# Back.net
KiCad netlist of a schematic drawn in Altium Designer
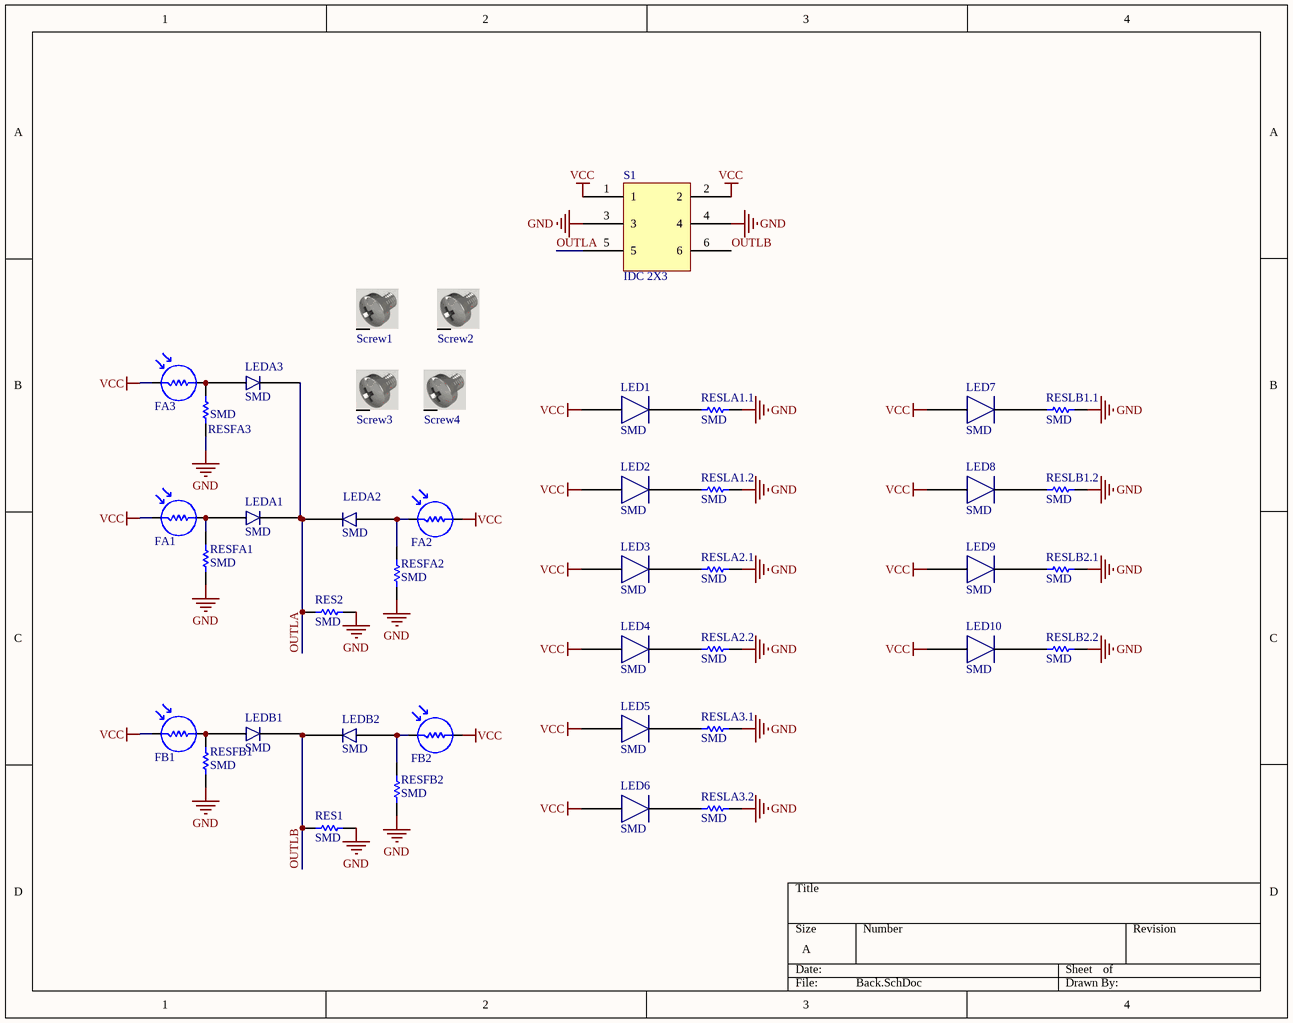
[diagram p0: Back.SchDoc]

(export (version "E")
  (design (tool "Eeschema 10.0.6"))
  (components
    (comp (ref "FA1")
      (value "Photo Cell")
      (footprint "PhotoCell.")
      (fields (field (name "PUBLISHER") "Altium Limited"))
      (libsource (lib "Farzanegan") (part "Photo Cell.."))
    )
    (comp (ref "FA2")
      (value "Photo Cell")
      (footprint "PhotoCell.")
      (fields (field (name "PUBLISHER") "Altium Limited"))
      (libsource (lib "Farzanegan") (part "Photo Cell.."))
    )
    (comp (ref "FA3")
      (value "Photo Cell")
      (footprint "PhotoCell.")
      (fields (field (name "PUBLISHER") "Altium Limited"))
      (libsource (lib "Farzanegan") (part "Photo Cell.."))
    )
    (comp (ref "FB1")
      (value "Photo Cell")
      (footprint "PhotoCell.")
      (fields (field (name "PUBLISHER") "Altium Limited"))
      (libsource (lib "Farzanegan") (part "Photo Cell.."))
    )
    (comp (ref "FB2")
      (value "Photo Cell")
      (footprint "PhotoCell.")
      (fields (field (name "PUBLISHER") "Altium Limited"))
      (libsource (lib "Farzanegan") (part "Photo Cell.."))
    )
    (comp (ref "LED1") (value "SMD") (footprint "LED SMD") (libsource (lib "Farzanegan") (part "LED SMD")))
    (comp (ref "LED2") (value "SMD") (footprint "LED SMD") (libsource (lib "Farzanegan") (part "LED SMD")))
    (comp (ref "LED3") (value "SMD") (footprint "LED SMD") (libsource (lib "Farzanegan") (part "LED SMD")))
    (comp (ref "LED4") (value "SMD") (footprint "LED SMD") (libsource (lib "Farzanegan") (part "LED SMD")))
    (comp (ref "LED5") (value "SMD") (footprint "LED SMD") (libsource (lib "Farzanegan") (part "LED SMD")))
    (comp (ref "LED6") (value "SMD") (footprint "LED SMD") (libsource (lib "Farzanegan") (part "LED SMD")))
    (comp (ref "LED7") (value "SMD") (footprint "LED SMD") (libsource (lib "Farzanegan") (part "LED SMD")))
    (comp (ref "LED8") (value "SMD") (footprint "LED SMD") (libsource (lib "Farzanegan") (part "LED SMD")))
    (comp (ref "LED9") (value "SMD") (footprint "LED SMD") (libsource (lib "Farzanegan") (part "LED SMD")))
    (comp (ref "LED10") (value "SMD") (footprint "LED SMD") (libsource (lib "Farzanegan") (part "LED SMD")))
    (comp (ref "LEDA1") (value "SMD") (footprint "LED SMD") (libsource (lib "") (part "LED SMD_1")))
    (comp (ref "LEDA2") (value "SMD") (footprint "LED SMD") (libsource (lib "") (part "LED SMD_1")))
    (comp (ref "LEDA3") (value "SMD") (footprint "LED SMD") (libsource (lib "") (part "LED SMD_1")))
    (comp (ref "LEDB1") (value "SMD") (footprint "LED SMD") (libsource (lib "") (part "LED SMD_1")))
    (comp (ref "LEDB2") (value "SMD") (footprint "LED SMD") (libsource (lib "") (part "LED SMD_1")))
    (comp (ref "RES1")
      (value "SMD")
      (footprint "Resistor SMD 1206")
      (libsource (lib "Farzanegan") (part "Res SMD"))
    )
    (comp (ref "RES2")
      (value "SMD")
      (footprint "Resistor SMD 1206")
      (libsource (lib "Farzanegan") (part "Res SMD"))
    )
    (comp (ref "RESFA1")
      (value "SMD")
      (footprint "Resistor SMD 1206")
      (libsource (lib "Farzanegan") (part "Res SMD"))
    )
    (comp (ref "RESFA2")
      (value "SMD")
      (footprint "Resistor SMD 1206")
      (libsource (lib "Farzanegan") (part "Res SMD"))
    )
    (comp (ref "RESFA3")
      (value "SMD")
      (footprint "Resistor SMD 1206")
      (libsource (lib "Farzanegan") (part "Res SMD"))
    )
    (comp (ref "RESFB1")
      (value "SMD")
      (footprint "Resistor SMD 1206")
      (libsource (lib "Farzanegan") (part "Res SMD"))
    )
    (comp (ref "RESFB2")
      (value "SMD")
      (footprint "Resistor SMD 1206")
      (libsource (lib "Farzanegan") (part "Res SMD"))
    )
    (comp (ref "RESLA1.1")
      (value "SMD")
      (footprint "Resistor SMD 1206")
      (libsource (lib "Farzanegan") (part "Res SMD"))
    )
    (comp (ref "RESLA1.2")
      (value "SMD")
      (footprint "Resistor SMD 1206")
      (libsource (lib "Farzanegan") (part "Res SMD"))
    )
    (comp (ref "RESLA2.1")
      (value "SMD")
      (footprint "Resistor SMD 1206")
      (libsource (lib "Farzanegan") (part "Res SMD"))
    )
    (comp (ref "RESLA2.2")
      (value "SMD")
      (footprint "Resistor SMD 1206")
      (libsource (lib "Farzanegan") (part "Res SMD"))
    )
    (comp (ref "RESLA3.1")
      (value "SMD")
      (footprint "Resistor SMD 1206")
      (libsource (lib "Farzanegan") (part "Res SMD"))
    )
    (comp (ref "RESLA3.2")
      (value "SMD")
      (footprint "Resistor SMD 1206")
      (libsource (lib "Farzanegan") (part "Res SMD"))
    )
    (comp (ref "RESLB1.1")
      (value "SMD")
      (footprint "Resistor SMD 1206")
      (libsource (lib "Farzanegan") (part "Res SMD"))
    )
    (comp (ref "RESLB1.2")
      (value "SMD")
      (footprint "Resistor SMD 1206")
      (libsource (lib "Farzanegan") (part "Res SMD"))
    )
    (comp (ref "RESLB2.1")
      (value "SMD")
      (footprint "Resistor SMD 1206")
      (libsource (lib "Farzanegan") (part "Res SMD"))
    )
    (comp (ref "RESLB2.2")
      (value "SMD")
      (footprint "Resistor SMD 1206")
      (libsource (lib "Farzanegan") (part "Res SMD"))
    )
    (comp (ref "S1") (value "IDC 2X3") (footprint "IDC 2X3") (libsource (lib "Farzanegan") (part "IDC 2X3")))
    (comp (ref "Screw1")
      (value "Screw")
      (footprint "Screw")
      (fields (field (name "PUBLISHER") "Altium Limited"))
      (libsource (lib "Farzanegan") (part "Screw"))
    )
    (comp (ref "Screw2")
      (value "Screw")
      (footprint "Screw")
      (fields (field (name "PUBLISHER") "Altium Limited"))
      (libsource (lib "Farzanegan") (part "Screw"))
    )
    (comp (ref "Screw3")
      (value "Screw")
      (footprint "Screw")
      (fields (field (name "PUBLISHER") "Altium Limited"))
      (libsource (lib "Farzanegan") (part "Screw"))
    )
    (comp (ref "Screw4")
      (value "Screw")
      (footprint "Screw")
      (fields (field (name "PUBLISHER") "Altium Limited"))
      (libsource (lib "Farzanegan") (part "Screw"))
    )
  )
  (nets
    (net (code "1") (name "/OUTLA") (class "Default")
      (node (ref "LEDA1") (pin "2") (pinfunction "2_2") (pintype "passive"))
      (node (ref "LEDA2") (pin "2") (pinfunction "2_2") (pintype "passive"))
      (node (ref "LEDA3") (pin "2") (pinfunction "2_2") (pintype "passive"))
      (node (ref "RES2") (pin "1") (pinfunction "1_1") (pintype "passive"))
      (node (ref "S1") (pin "5") (pinfunction "5_5") (pintype "passive"))
    )
    (net (code "2") (name "/OUTLB") (class "Default")
      (node (ref "LEDB1") (pin "2") (pinfunction "2_2") (pintype "passive"))
      (node (ref "LEDB2") (pin "2") (pinfunction "2_2") (pintype "passive"))
      (node (ref "RES1") (pin "1") (pinfunction "1_1") (pintype "passive"))
      (node (ref "S1") (pin "6") (pinfunction "6_6") (pintype "passive"))
    )
    (net (code "3") (name "GND") (class "Default")
      (node (ref "RES1") (pin "2") (pinfunction "2_2") (pintype "passive"))
      (node (ref "RES2") (pin "2") (pinfunction "2_2") (pintype "passive"))
      (node (ref "RESFA1") (pin "1") (pinfunction "1_1") (pintype "passive"))
      (node (ref "RESFA2") (pin "1") (pinfunction "1_1") (pintype "passive"))
      (node (ref "RESFA3") (pin "1") (pinfunction "1_1") (pintype "passive"))
      (node (ref "RESFB1") (pin "1") (pinfunction "1_1") (pintype "passive"))
      (node (ref "RESFB2") (pin "1") (pinfunction "1_1") (pintype "passive"))
      (node (ref "RESLA1.1") (pin "2") (pinfunction "2_2") (pintype "passive"))
      (node (ref "RESLA1.2") (pin "2") (pinfunction "2_2") (pintype "passive"))
      (node (ref "RESLA2.1") (pin "2") (pinfunction "2_2") (pintype "passive"))
      (node (ref "RESLA2.2") (pin "2") (pinfunction "2_2") (pintype "passive"))
      (node (ref "RESLA3.1") (pin "2") (pinfunction "2_2") (pintype "passive"))
      (node (ref "RESLA3.2") (pin "2") (pinfunction "2_2") (pintype "passive"))
      (node (ref "RESLB1.1") (pin "2") (pinfunction "2_2") (pintype "passive"))
      (node (ref "RESLB1.2") (pin "2") (pinfunction "2_2") (pintype "passive"))
      (node (ref "RESLB2.1") (pin "2") (pinfunction "2_2") (pintype "passive"))
      (node (ref "RESLB2.2") (pin "2") (pinfunction "2_2") (pintype "passive"))
      (node (ref "S1") (pin "3") (pinfunction "3_3") (pintype "passive"))
      (node (ref "S1") (pin "4") (pinfunction "4_4") (pintype "passive"))
    )
    (net (code "4") (name "Net-(FA1-Pad2)") (class "Default")
      (node (ref "FA1") (pin "2") (pintype "passive"))
      (node (ref "LEDA1") (pin "1") (pinfunction "1_1") (pintype "passive"))
      (node (ref "RESFA1") (pin "2") (pinfunction "2_2") (pintype "passive"))
    )
    (net (code "5") (name "Net-(FA2-Pad1)") (class "Default")
      (node (ref "FA2") (pin "1") (pintype "passive"))
      (node (ref "LEDA2") (pin "1") (pinfunction "1_1") (pintype "passive"))
      (node (ref "RESFA2") (pin "2") (pinfunction "2_2") (pintype "passive"))
    )
    (net (code "6") (name "Net-(FA3-Pad2)") (class "Default")
      (node (ref "FA3") (pin "2") (pintype "passive"))
      (node (ref "LEDA3") (pin "1") (pinfunction "1_1") (pintype "passive"))
      (node (ref "RESFA3") (pin "2") (pinfunction "2_2") (pintype "passive"))
    )
    (net (code "7") (name "Net-(FB1-Pad2)") (class "Default")
      (node (ref "FB1") (pin "2") (pintype "passive"))
      (node (ref "LEDB1") (pin "1") (pinfunction "1_1") (pintype "passive"))
      (node (ref "RESFB1") (pin "2") (pinfunction "2_2") (pintype "passive"))
    )
    (net (code "8") (name "Net-(FB2-Pad1)") (class "Default")
      (node (ref "FB2") (pin "1") (pintype "passive"))
      (node (ref "LEDB2") (pin "1") (pinfunction "1_1") (pintype "passive"))
      (node (ref "RESFB2") (pin "2") (pinfunction "2_2") (pintype "passive"))
    )
    (net (code "9") (name "VCC") (class "Default")
      (node (ref "FA1") (pin "1") (pintype "passive"))
      (node (ref "FA2") (pin "2") (pintype "passive"))
      (node (ref "FA3") (pin "1") (pintype "passive"))
      (node (ref "FB1") (pin "1") (pintype "passive"))
      (node (ref "FB2") (pin "2") (pintype "passive"))
      (node (ref "LED1") (pin "1") (pinfunction "1_1") (pintype "passive"))
      (node (ref "LED10") (pin "1") (pinfunction "1_1") (pintype "passive"))
      (node (ref "LED2") (pin "1") (pinfunction "1_1") (pintype "passive"))
      (node (ref "LED3") (pin "1") (pinfunction "1_1") (pintype "passive"))
      (node (ref "LED4") (pin "1") (pinfunction "1_1") (pintype "passive"))
      (node (ref "LED5") (pin "1") (pinfunction "1_1") (pintype "passive"))
      (node (ref "LED6") (pin "1") (pinfunction "1_1") (pintype "passive"))
      (node (ref "LED7") (pin "1") (pinfunction "1_1") (pintype "passive"))
      (node (ref "LED8") (pin "1") (pinfunction "1_1") (pintype "passive"))
      (node (ref "LED9") (pin "1") (pinfunction "1_1") (pintype "passive"))
      (node (ref "S1") (pin "1") (pinfunction "1_1") (pintype "passive"))
      (node (ref "S1") (pin "2") (pinfunction "2_2") (pintype "passive"))
    )
    (net (code "10") (name "unconnected-(LED1-Pad2)") (class "Default")
      (node (ref "LED1") (pin "2") (pinfunction "2_2") (pintype "passive"))
    )
    (net (code "11") (name "unconnected-(LED2-Pad2)") (class "Default")
      (node (ref "LED2") (pin "2") (pinfunction "2_2") (pintype "passive"))
    )
    (net (code "12") (name "unconnected-(LED3-Pad2)") (class "Default")
      (node (ref "LED3") (pin "2") (pinfunction "2_2") (pintype "passive"))
    )
    (net (code "13") (name "unconnected-(LED4-Pad2)") (class "Default")
      (node (ref "LED4") (pin "2") (pinfunction "2_2") (pintype "passive"))
    )
    (net (code "14") (name "unconnected-(LED5-Pad2)") (class "Default")
      (node (ref "LED5") (pin "2") (pinfunction "2_2") (pintype "passive"))
    )
    (net (code "15") (name "unconnected-(LED6-Pad2)") (class "Default")
      (node (ref "LED6") (pin "2") (pinfunction "2_2") (pintype "passive"))
    )
    (net (code "16") (name "unconnected-(LED7-Pad2)") (class "Default")
      (node (ref "LED7") (pin "2") (pinfunction "2_2") (pintype "passive"))
    )
    (net (code "17") (name "unconnected-(LED8-Pad2)") (class "Default")
      (node (ref "LED8") (pin "2") (pinfunction "2_2") (pintype "passive"))
    )
    (net (code "18") (name "unconnected-(LED9-Pad2)") (class "Default")
      (node (ref "LED9") (pin "2") (pinfunction "2_2") (pintype "passive"))
    )
    (net (code "19") (name "unconnected-(LED10-Pad2)") (class "Default")
      (node (ref "LED10") (pin "2") (pinfunction "2_2") (pintype "passive"))
    )
    (net (code "20") (name "unconnected-(RESLA1.1-Pad1)") (class "Default")
      (node (ref "RESLA1.1") (pin "1") (pinfunction "1_1") (pintype "passive"))
    )
    (net (code "21") (name "unconnected-(RESLA1.2-Pad1)") (class "Default")
      (node (ref "RESLA1.2") (pin "1") (pinfunction "1_1") (pintype "passive"))
    )
    (net (code "22") (name "unconnected-(RESLA2.1-Pad1)") (class "Default")
      (node (ref "RESLA2.1") (pin "1") (pinfunction "1_1") (pintype "passive"))
    )
    (net (code "23") (name "unconnected-(RESLA2.2-Pad1)") (class "Default")
      (node (ref "RESLA2.2") (pin "1") (pinfunction "1_1") (pintype "passive"))
    )
    (net (code "24") (name "unconnected-(RESLA3.1-Pad1)") (class "Default")
      (node (ref "RESLA3.1") (pin "1") (pinfunction "1_1") (pintype "passive"))
    )
    (net (code "25") (name "unconnected-(RESLA3.2-Pad1)") (class "Default")
      (node (ref "RESLA3.2") (pin "1") (pinfunction "1_1") (pintype "passive"))
    )
    (net (code "26") (name "unconnected-(RESLB1.1-Pad1)") (class "Default")
      (node (ref "RESLB1.1") (pin "1") (pinfunction "1_1") (pintype "passive"))
    )
    (net (code "27") (name "unconnected-(RESLB1.2-Pad1)") (class "Default")
      (node (ref "RESLB1.2") (pin "1") (pinfunction "1_1") (pintype "passive"))
    )
    (net (code "28") (name "unconnected-(RESLB2.1-Pad1)") (class "Default")
      (node (ref "RESLB2.1") (pin "1") (pinfunction "1_1") (pintype "passive"))
    )
    (net (code "29") (name "unconnected-(RESLB2.2-Pad1)") (class "Default")
      (node (ref "RESLB2.2") (pin "1") (pinfunction "1_1") (pintype "passive"))
    )
    (net (code "30") (name "unconnected-(Screw1-PadS)") (class "Default")
      (node (ref "Screw1") (pin "S") (pinfunction "S_S") (pintype "passive"))
    )
    (net (code "31") (name "unconnected-(Screw2-PadS)") (class "Default")
      (node (ref "Screw2") (pin "S") (pinfunction "S_S") (pintype "passive"))
    )
    (net (code "32") (name "unconnected-(Screw3-PadS)") (class "Default")
      (node (ref "Screw3") (pin "S") (pinfunction "S_S") (pintype "passive"))
    )
    (net (code "33") (name "unconnected-(Screw4-PadS)") (class "Default")
      (node (ref "Screw4") (pin "S") (pinfunction "S_S") (pintype "passive"))
    )
  )
)
